# Controller_Board.net
KiCad netlist of a schematic drawn in EAGLE
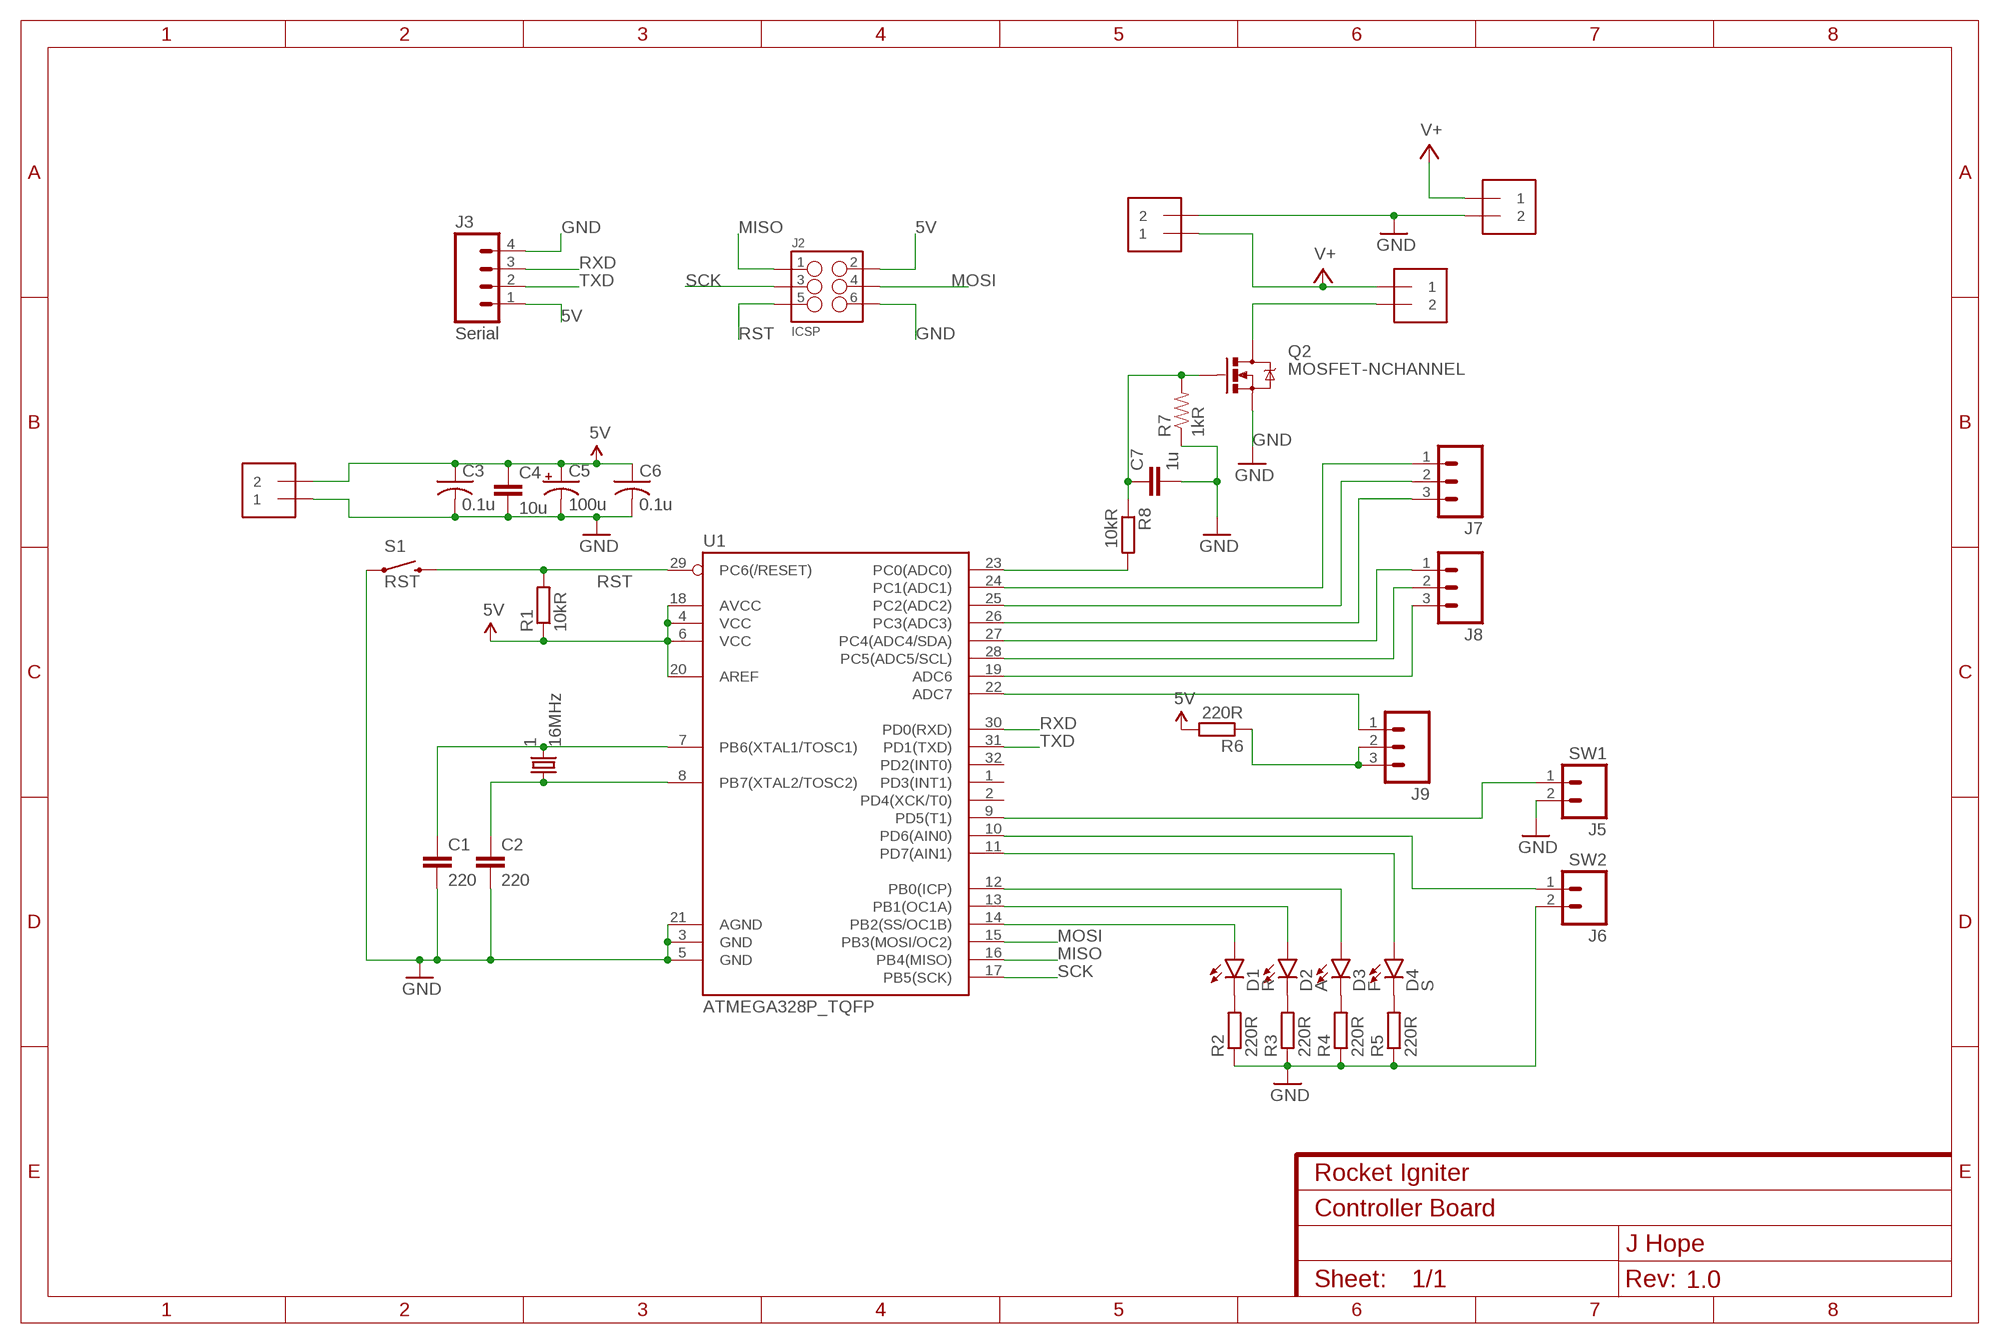
[diagram p0: schematic, sheet 1]

(export (version "E")
  (design (tool "Eeschema 10.0.6"))
  (components
    (comp (ref "1")
      (value "16MHz")
      (footprint "eagle-import:CRYSTAL-OSC-SMD-5X3.2")
      (libsource (lib "eagle-import") (part "CRYSTAL4"))
    )
    (comp (ref "C1")
      (value "220")
      (footprint "eagle-import:C0603")
      (libsource (lib "eagle-import") (part "C-EUC0603"))
    )
    (comp (ref "C2")
      (value "220")
      (footprint "eagle-import:C0603")
      (libsource (lib "eagle-import") (part "C-EUC0603"))
    )
    (comp (ref "C3")
      (value "0.1u")
      (footprint "eagle-import:C0603")
      (libsource (lib "eagle-import") (part "C-USC0603"))
    )
    (comp (ref "C4")
      (value "10u")
      (footprint "eagle-import:0603-CAP")
      (libsource (lib "eagle-import") (part "CAP0603-CAP"))
    )
    (comp (ref "C5")
      (value "100u")
      (footprint "eagle-import:PANASONIC_D")
      (libsource (lib "eagle-import") (part "CAP_POLD"))
    )
    (comp (ref "C6")
      (value "0.1u")
      (footprint "eagle-import:C0603")
      (libsource (lib "eagle-import") (part "C-USC0603"))
    )
    (comp (ref "C7")
      (value "1u")
      (footprint "eagle-import:0603-CAP")
      (libsource (lib "eagle-import") (part "CAP0603-CAP"))
    )
    (comp (ref "D1")
      (value "R")
      (footprint "eagle-import:LED5MM")
      (libsource (lib "eagle-import") (part "LED5MM"))
    )
    (comp (ref "D2")
      (value "A")
      (footprint "eagle-import:LED5MM")
      (libsource (lib "eagle-import") (part "LED5MM"))
    )
    (comp (ref "D3")
      (value "F")
      (footprint "eagle-import:LED5MM")
      (libsource (lib "eagle-import") (part "LED5MM"))
    )
    (comp (ref "D4")
      (value "S")
      (footprint "eagle-import:LED5MM")
      (libsource (lib "eagle-import") (part "LED5MM"))
    )
    (comp (ref "FAN")
      (value "FAN")
      (footprint "eagle-import:1X2-3.5MM")
      (libsource (lib "eagle-import") (part "1X2-3.5MM"))
    )
    (comp (ref "HV")
      (value "HV")
      (footprint "eagle-import:1X2-3.5MM")
      (libsource (lib "eagle-import") (part "1X2-3.5MM"))
    )
    (comp (ref "J2")
      (value "ICSP")
      (footprint "eagle-import:2X3")
      (libsource (lib "eagle-import") (part "M03X22X3_SILK_MALE_PTH"))
    )
    (comp (ref "J3")
      (value "Serial")
      (footprint "eagle-import:1X04")
      (libsource (lib "eagle-import") (part "M04PTH"))
    )
    (comp (ref "J5")
      (value "SW1")
      (footprint "eagle-import:1X02_POLAR")
      (libsource (lib "eagle-import") (part "M02SMALLPOLAR"))
    )
    (comp (ref "J6")
      (value "SW2")
      (footprint "eagle-import:1X02_POLAR")
      (libsource (lib "eagle-import") (part "M02SMALLPOLAR"))
    )
    (comp (ref "J7")
      (value "M03PTH")
      (footprint "eagle-import:1X03")
      (libsource (lib "eagle-import") (part "M03PTH"))
    )
    (comp (ref "J8")
      (value "M03PTH")
      (footprint "eagle-import:1X03")
      (libsource (lib "eagle-import") (part "M03PTH"))
    )
    (comp (ref "J9")
      (value "M03PTH")
      (footprint "eagle-import:1X03")
      (libsource (lib "eagle-import") (part "M03PTH"))
    )
    (comp (ref "POWER")
      (value "+5V")
      (footprint "eagle-import:1X2-3.5MM")
      (libsource (lib "eagle-import") (part "1X2-3.5MM"))
    )
    (comp (ref "Q2")
      (value "MOSFET-NCHANNEL")
      (footprint "eagle-import:TO220V")
      (libsource (lib "eagle-import") (part "MOSFET-NCHANNELFQP30N06L"))
    )
    (comp (ref "R1")
      (value "10kR")
      (footprint "eagle-import:R0603")
      (libsource (lib "eagle-import") (part "R-EU_R0603"))
    )
    (comp (ref "R2")
      (value "220R")
      (footprint "eagle-import:R0603")
      (libsource (lib "eagle-import") (part "R-EU_R0603"))
    )
    (comp (ref "R3")
      (value "220R")
      (footprint "eagle-import:R0603")
      (libsource (lib "eagle-import") (part "R-EU_R0603"))
    )
    (comp (ref "R4")
      (value "220R")
      (footprint "eagle-import:R0603")
      (libsource (lib "eagle-import") (part "R-EU_R0603"))
    )
    (comp (ref "R5")
      (value "220R")
      (footprint "eagle-import:R0603")
      (libsource (lib "eagle-import") (part "R-EU_R0603"))
    )
    (comp (ref "R6")
      (value "220R")
      (footprint "eagle-import:R0603")
      (libsource (lib "eagle-import") (part "R-EU_R0603"))
    )
    (comp (ref "R7")
      (value "1kR")
      (footprint "eagle-import:0603-RES")
      (libsource (lib "eagle-import") (part "RESISTOR0603"))
    )
    (comp (ref "R8")
      (value "10kR")
      (footprint "eagle-import:R0603")
      (libsource (lib "eagle-import") (part "R-EU_R0603"))
    )
    (comp (ref "S1")
      (value "RST")
      (footprint "eagle-import:TACTILE-SWITCH-1101NE")
      (libsource (lib "eagle-import") (part "SWITCH-MOMENTARY-2SMD-1101NE"))
    )
    (comp (ref "U1")
      (value "ATMEGA328P_TQFP")
      (footprint "eagle-import:TQFP32-08")
      (libsource (lib "eagle-import") (part "ATMEGA328P_TQFP"))
    )
    (comp (ref "V+")
      (value "V+")
      (footprint "eagle-import:1X2-3.5MM")
      (libsource (lib "eagle-import") (part "1X2-3.5MM"))
    )
  )
  (nets
    (net (code "1") (name "/MISO") (class "Default")
      (node (ref "J2") (pin "1") (pinfunction "1_1") (pintype "bidirectional"))
      (node (ref "U1") (pin "16") (pinfunction "PB4(MISO)_16") (pintype "bidirectional"))
    )
    (net (code "2") (name "/MOSI") (class "Default")
      (node (ref "J2") (pin "4") (pinfunction "4_4") (pintype "bidirectional"))
      (node (ref "U1") (pin "15") (pinfunction "PB3(MOSI/OC2)_15") (pintype "bidirectional"))
    )
    (net (code "3") (name "/RST") (class "Default")
      (node (ref "J2") (pin "5") (pinfunction "5_5") (pintype "bidirectional"))
      (node (ref "R1") (pin "2") (pinfunction "2_2") (pintype "passive"))
      (node (ref "S1") (pin "2") (pinfunction "2_2") (pintype "passive"))
      (node (ref "U1") (pin "29") (pinfunction "PC6(/RESET)_29") (pintype "bidirectional"))
    )
    (net (code "4") (name "/RXD") (class "Default")
      (node (ref "J3") (pin "3") (pinfunction "3_3") (pintype "passive"))
      (node (ref "U1") (pin "30") (pinfunction "PD0(RXD)_30") (pintype "bidirectional"))
    )
    (net (code "5") (name "/SCK") (class "Default")
      (node (ref "J2") (pin "3") (pinfunction "3_3") (pintype "bidirectional"))
      (node (ref "U1") (pin "17") (pinfunction "PB5(SCK)_17") (pintype "bidirectional"))
    )
    (net (code "6") (name "/TXD") (class "Default")
      (node (ref "J3") (pin "2") (pinfunction "2_2") (pintype "passive"))
      (node (ref "U1") (pin "31") (pinfunction "PD1(TXD)_31") (pintype "bidirectional"))
    )
    (net (code "7") (name "5V") (class "Default")
      (node (ref "C3") (pin "1") (pinfunction "1_1") (pintype "passive"))
      (node (ref "C4") (pin "1") (pinfunction "1_1") (pintype "passive"))
      (node (ref "C5") (pin "+") (pinfunction "+_+") (pintype "passive"))
      (node (ref "C6") (pin "1") (pinfunction "1_1") (pintype "passive"))
      (node (ref "J2") (pin "2") (pinfunction "2_2") (pintype "bidirectional"))
      (node (ref "J3") (pin "1") (pinfunction "1_1") (pintype "passive"))
      (node (ref "POWER") (pin "2") (pinfunction "2_2") (pintype "passive"))
      (node (ref "R1") (pin "1") (pinfunction "1_1") (pintype "passive"))
      (node (ref "R6") (pin "2") (pinfunction "2_2") (pintype "passive"))
      (node (ref "U1") (pin "18") (pinfunction "AVCC_18") (pintype "bidirectional"))
      (node (ref "U1") (pin "20") (pinfunction "AREF_20") (pintype "bidirectional"))
      (node (ref "U1") (pin "4") (pinfunction "VCC_4") (pintype "bidirectional"))
      (node (ref "U1") (pin "6") (pinfunction "VCC_6") (pintype "bidirectional"))
    )
    (net (code "8") (name "GND") (class "Default")
      (node (ref "C1") (pin "2") (pinfunction "2_2") (pintype "passive"))
      (node (ref "C2") (pin "2") (pinfunction "2_2") (pintype "passive"))
      (node (ref "C3") (pin "2") (pinfunction "2_2") (pintype "passive"))
      (node (ref "C4") (pin "2") (pinfunction "2_2") (pintype "passive"))
      (node (ref "C5") (pin "-") (pinfunction "-_-") (pintype "passive"))
      (node (ref "C6") (pin "2") (pinfunction "2_2") (pintype "passive"))
      (node (ref "C7") (pin "2") (pinfunction "2_2") (pintype "passive"))
      (node (ref "FAN") (pin "2") (pinfunction "2_2") (pintype "passive"))
      (node (ref "J2") (pin "6") (pinfunction "6_6") (pintype "bidirectional"))
      (node (ref "J3") (pin "4") (pinfunction "4_4") (pintype "passive"))
      (node (ref "J5") (pin "2") (pinfunction "2_2") (pintype "passive"))
      (node (ref "J6") (pin "2") (pinfunction "2_2") (pintype "passive"))
      (node (ref "POWER") (pin "1") (pinfunction "1_1") (pintype "passive"))
      (node (ref "Q2") (pin "3") (pinfunction "S_3") (pintype "passive"))
      (node (ref "R2") (pin "1") (pinfunction "1_1") (pintype "passive"))
      (node (ref "R3") (pin "1") (pinfunction "1_1") (pintype "passive"))
      (node (ref "R4") (pin "1") (pinfunction "1_1") (pintype "passive"))
      (node (ref "R5") (pin "1") (pinfunction "1_1") (pintype "passive"))
      (node (ref "R7") (pin "1") (pinfunction "1_1") (pintype "passive"))
      (node (ref "S1") (pin "1") (pinfunction "1_1") (pintype "passive"))
      (node (ref "U1") (pin "21") (pinfunction "AGND_21") (pintype "bidirectional"))
      (node (ref "U1") (pin "3") (pinfunction "GND_3") (pintype "bidirectional"))
      (node (ref "U1") (pin "5") (pinfunction "GND_5") (pintype "bidirectional"))
      (node (ref "V+") (pin "2") (pinfunction "2_2") (pintype "passive"))
    )
    (net (code "9") (name "Net-(1-2)") (class "Default")
      (node (ref "1") (pin "3") (pinfunction "2_3") (pintype "passive"))
      (node (ref "C1") (pin "1") (pinfunction "1_1") (pintype "passive"))
      (node (ref "U1") (pin "7") (pinfunction "PB6(XTAL1/TOSC1)_7") (pintype "bidirectional"))
    )
    (net (code "10") (name "Net-(D1-C)") (class "Default")
      (node (ref "D1") (pin "K") (pinfunction "C_K") (pintype "passive"))
      (node (ref "R2") (pin "2") (pinfunction "2_2") (pintype "passive"))
    )
    (net (code "11") (name "Net-(D2-C)") (class "Default")
      (node (ref "D2") (pin "K") (pinfunction "C_K") (pintype "passive"))
      (node (ref "R3") (pin "2") (pinfunction "2_2") (pintype "passive"))
    )
    (net (code "12") (name "Net-(D3-C)") (class "Default")
      (node (ref "D3") (pin "K") (pinfunction "C_K") (pintype "passive"))
      (node (ref "R4") (pin "2") (pinfunction "2_2") (pintype "passive"))
    )
    (net (code "13") (name "Net-(D4-C)") (class "Default")
      (node (ref "D4") (pin "K") (pinfunction "C_K") (pintype "passive"))
      (node (ref "R5") (pin "2") (pinfunction "2_2") (pintype "passive"))
    )
    (net (code "14") (name "Net-(J9-Pad2)") (class "Default")
      (node (ref "J9") (pin "2") (pinfunction "2_2") (pintype "passive"))
      (node (ref "J9") (pin "3") (pinfunction "3_3") (pintype "passive"))
      (node (ref "R6") (pin "1") (pinfunction "1_1") (pintype "passive"))
    )
    (net (code "15") (name "Net-(Q2-D)") (class "Default")
      (node (ref "HV") (pin "2") (pinfunction "2_2") (pintype "passive"))
      (node (ref "Q2") (pin "2") (pinfunction "D_2") (pintype "passive"))
    )
    (net (code "16") (name "Net-(Q2-G)") (class "Default")
      (node (ref "C7") (pin "1") (pinfunction "1_1") (pintype "passive"))
      (node (ref "Q2") (pin "1") (pinfunction "G_1") (pintype "passive"))
      (node (ref "R7") (pin "2") (pinfunction "2_2") (pintype "passive"))
      (node (ref "R8") (pin "1") (pinfunction "1_1") (pintype "passive"))
    )
    (net (code "17") (name "Net-(U1-ADC6)") (class "Default")
      (node (ref "J8") (pin "3") (pinfunction "3_3") (pintype "passive"))
      (node (ref "U1") (pin "19") (pinfunction "ADC6_19") (pintype "bidirectional"))
    )
    (net (code "18") (name "Net-(U1-ADC7)") (class "Default")
      (node (ref "J9") (pin "1") (pinfunction "1_1") (pintype "passive"))
      (node (ref "U1") (pin "22") (pinfunction "ADC7_22") (pintype "bidirectional"))
    )
    (net (code "19") (name "Net-(U1-PB0(ICP))") (class "Default")
      (node (ref "D3") (pin "A") (pinfunction "A_A") (pintype "passive"))
      (node (ref "U1") (pin "12") (pinfunction "PB0(ICP)_12") (pintype "bidirectional"))
    )
    (net (code "20") (name "Net-(U1-PB1(OC1A))") (class "Default")
      (node (ref "D2") (pin "A") (pinfunction "A_A") (pintype "passive"))
      (node (ref "U1") (pin "13") (pinfunction "PB1(OC1A)_13") (pintype "bidirectional"))
    )
    (net (code "21") (name "Net-(U1-PB2(SS{slash}OC1B))") (class "Default")
      (node (ref "D1") (pin "A") (pinfunction "A_A") (pintype "passive"))
      (node (ref "U1") (pin "14") (pinfunction "PB2(SS/OC1B)_14") (pintype "bidirectional"))
    )
    (net (code "22") (name "Net-(U1-PB7(XTAL2{slash}TOSC2))") (class "Default")
      (node (ref "1") (pin "1") (pinfunction "1_1") (pintype "passive"))
      (node (ref "C2") (pin "1") (pinfunction "1_1") (pintype "passive"))
      (node (ref "U1") (pin "8") (pinfunction "PB7(XTAL2/TOSC2)_8") (pintype "bidirectional"))
    )
    (net (code "23") (name "Net-(U1-PC0(ADC0))") (class "Default")
      (node (ref "R8") (pin "2") (pinfunction "2_2") (pintype "passive"))
      (node (ref "U1") (pin "23") (pinfunction "PC0(ADC0)_23") (pintype "bidirectional"))
    )
    (net (code "24") (name "Net-(U1-PC1(ADC1))") (class "Default")
      (node (ref "J7") (pin "1") (pinfunction "1_1") (pintype "passive"))
      (node (ref "U1") (pin "24") (pinfunction "PC1(ADC1)_24") (pintype "bidirectional"))
    )
    (net (code "25") (name "Net-(U1-PC2(ADC2))") (class "Default")
      (node (ref "J7") (pin "2") (pinfunction "2_2") (pintype "passive"))
      (node (ref "U1") (pin "25") (pinfunction "PC2(ADC2)_25") (pintype "bidirectional"))
    )
    (net (code "26") (name "Net-(U1-PC3(ADC3))") (class "Default")
      (node (ref "J7") (pin "3") (pinfunction "3_3") (pintype "passive"))
      (node (ref "U1") (pin "26") (pinfunction "PC3(ADC3)_26") (pintype "bidirectional"))
    )
    (net (code "27") (name "Net-(U1-PC4(ADC4{slash}SDA))") (class "Default")
      (node (ref "J8") (pin "1") (pinfunction "1_1") (pintype "passive"))
      (node (ref "U1") (pin "27") (pinfunction "PC4(ADC4/SDA)_27") (pintype "bidirectional"))
    )
    (net (code "28") (name "Net-(U1-PC5(ADC5{slash}SCL))") (class "Default")
      (node (ref "J8") (pin "2") (pinfunction "2_2") (pintype "passive"))
      (node (ref "U1") (pin "28") (pinfunction "PC5(ADC5/SCL)_28") (pintype "bidirectional"))
    )
    (net (code "29") (name "Net-(U1-PD5(T1))") (class "Default")
      (node (ref "J5") (pin "1") (pinfunction "1_1") (pintype "passive"))
      (node (ref "U1") (pin "9") (pinfunction "PD5(T1)_9") (pintype "bidirectional"))
    )
    (net (code "30") (name "Net-(U1-PD6(AIN0))") (class "Default")
      (node (ref "J6") (pin "1") (pinfunction "1_1") (pintype "passive"))
      (node (ref "U1") (pin "10") (pinfunction "PD6(AIN0)_10") (pintype "bidirectional"))
    )
    (net (code "31") (name "Net-(U1-PD7(AIN1))") (class "Default")
      (node (ref "D4") (pin "A") (pinfunction "A_A") (pintype "passive"))
      (node (ref "U1") (pin "11") (pinfunction "PD7(AIN1)_11") (pintype "bidirectional"))
    )
    (net (code "32") (name "V+") (class "Default")
      (node (ref "FAN") (pin "1") (pinfunction "1_1") (pintype "passive"))
      (node (ref "HV") (pin "1") (pinfunction "1_1") (pintype "passive"))
      (node (ref "V+") (pin "1") (pinfunction "1_1") (pintype "passive"))
    )
    (net (code "33") (name "unconnected-(U1-PD2(INT0)-Pad32)") (class "Default")
      (node (ref "U1") (pin "32") (pinfunction "PD2(INT0)_32") (pintype "bidirectional"))
    )
    (net (code "34") (name "unconnected-(U1-PD3(INT1)-Pad1)") (class "Default")
      (node (ref "U1") (pin "1") (pinfunction "PD3(INT1)_1") (pintype "bidirectional"))
    )
    (net (code "35") (name "unconnected-(U1-PD4(XCK{slash}T0)-Pad2)") (class "Default")
      (node (ref "U1") (pin "2") (pinfunction "PD4(XCK/T0)_2") (pintype "bidirectional"))
    )
  )
)
